# R111X.net
KiCad netlist of a schematic drawn in EAGLE
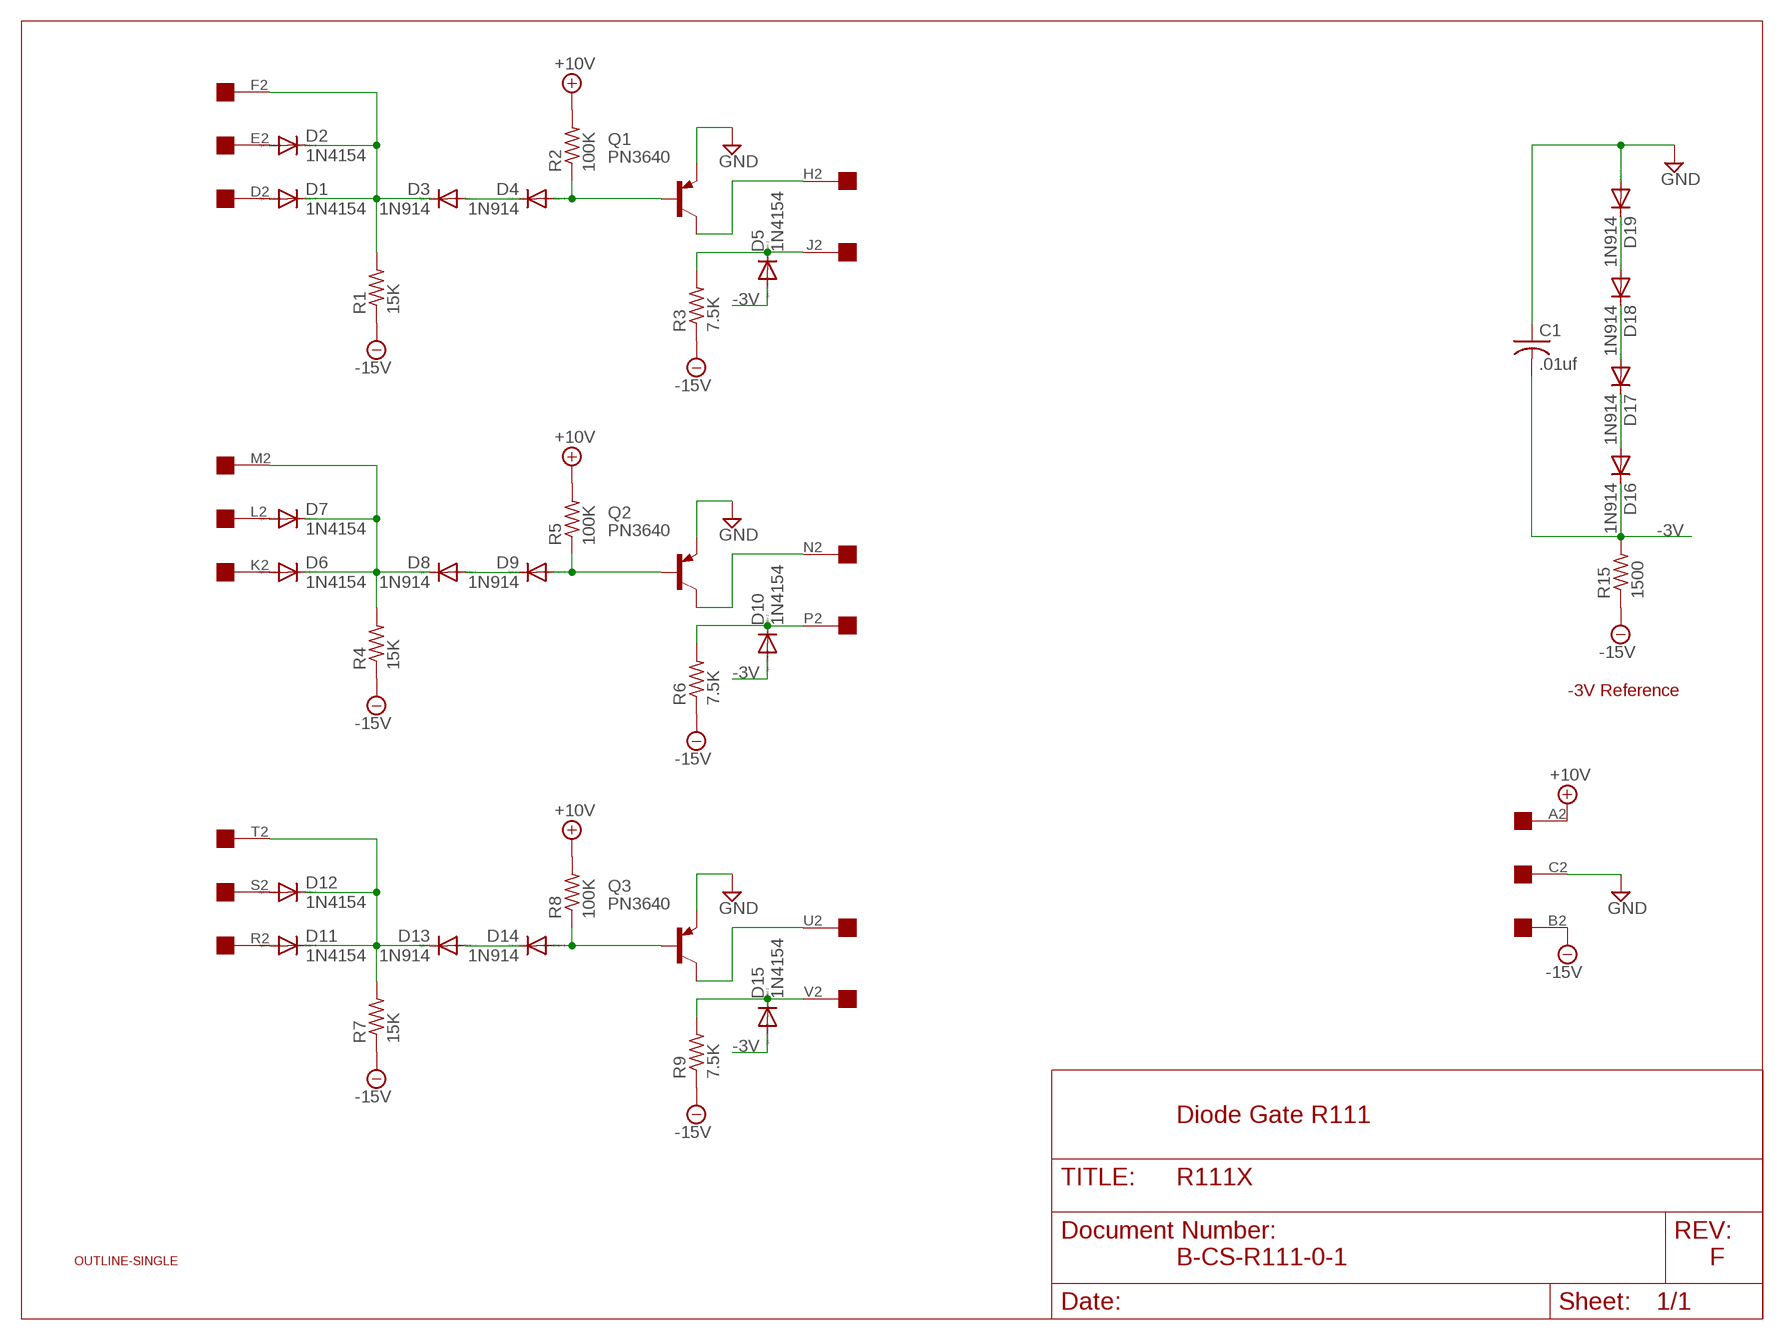
[diagram p0: schematic, sheet 1]

(export (version "E")
  (design (tool "Eeschema 10.0.6"))
  (components
    (comp (ref "C1")
      (value ".01uf")
      (footprint "eagle-import:C063-025X075")
      (libsource (lib "eagle-import") (part "C-US"))
    )
    (comp (ref "D1")
      (value "1N4154")
      (footprint "eagle-import:DO35-10")
      (libsource (lib "eagle-import") (part "1N4148DO35-10"))
    )
    (comp (ref "D2")
      (value "1N4154")
      (footprint "eagle-import:DO35-10")
      (libsource (lib "eagle-import") (part "1N4148DO35-10"))
    )
    (comp (ref "D3")
      (value "1N914")
      (footprint "eagle-import:DO35-10")
      (libsource (lib "eagle-import") (part "1N4148DO35-10"))
    )
    (comp (ref "D4")
      (value "1N914")
      (footprint "eagle-import:DO35-10")
      (libsource (lib "eagle-import") (part "1N4148DO35-10"))
    )
    (comp (ref "D5")
      (value "1N4154")
      (footprint "eagle-import:DO35-10")
      (libsource (lib "eagle-import") (part "1N4148DO35-10"))
    )
    (comp (ref "D6")
      (value "1N4154")
      (footprint "eagle-import:DO35-10")
      (libsource (lib "eagle-import") (part "1N4148DO35-10"))
    )
    (comp (ref "D7")
      (value "1N4154")
      (footprint "eagle-import:DO35-10")
      (libsource (lib "eagle-import") (part "1N4148DO35-10"))
    )
    (comp (ref "D8")
      (value "1N914")
      (footprint "eagle-import:DO35-10")
      (libsource (lib "eagle-import") (part "1N4148DO35-10"))
    )
    (comp (ref "D9")
      (value "1N914")
      (footprint "eagle-import:DO35-10")
      (libsource (lib "eagle-import") (part "1N4148DO35-10"))
    )
    (comp (ref "D10")
      (value "1N4154")
      (footprint "eagle-import:DO35-10")
      (libsource (lib "eagle-import") (part "1N4148DO35-10"))
    )
    (comp (ref "D11")
      (value "1N4154")
      (footprint "eagle-import:DO35-10")
      (libsource (lib "eagle-import") (part "1N4148DO35-10"))
    )
    (comp (ref "D12")
      (value "1N4154")
      (footprint "eagle-import:DO35-10")
      (libsource (lib "eagle-import") (part "1N4148DO35-10"))
    )
    (comp (ref "D13")
      (value "1N914")
      (footprint "eagle-import:DO35-10")
      (libsource (lib "eagle-import") (part "1N4148DO35-10"))
    )
    (comp (ref "D14")
      (value "1N914")
      (footprint "eagle-import:DO35-10")
      (libsource (lib "eagle-import") (part "1N4148DO35-10"))
    )
    (comp (ref "D15")
      (value "1N4154")
      (footprint "eagle-import:DO35-10")
      (libsource (lib "eagle-import") (part "1N4148DO35-10"))
    )
    (comp (ref "D16")
      (value "1N914")
      (footprint "eagle-import:DO35-10")
      (libsource (lib "eagle-import") (part "1N4148DO35-10"))
    )
    (comp (ref "D17")
      (value "1N914")
      (footprint "eagle-import:DO35-10")
      (libsource (lib "eagle-import") (part "1N4148DO35-10"))
    )
    (comp (ref "D18")
      (value "1N914")
      (footprint "eagle-import:DO35-10")
      (libsource (lib "eagle-import") (part "1N4148DO35-10"))
    )
    (comp (ref "D19")
      (value "1N914")
      (footprint "eagle-import:DO35-10")
      (libsource (lib "eagle-import") (part "1N4148DO35-10"))
    )
    (comp (ref "Q1")
      (value "PN3640")
      (footprint "eagle-import:TO39")
      (libsource (lib "eagle-import") (part "2N3637"))
    )
    (comp (ref "Q2")
      (value "PN3640")
      (footprint "eagle-import:TO39")
      (libsource (lib "eagle-import") (part "2N3637"))
    )
    (comp (ref "Q3")
      (value "PN3640")
      (footprint "eagle-import:TO39")
      (libsource (lib "eagle-import") (part "2N3637"))
    )
    (comp (ref "R1")
      (value "15K")
      (footprint "eagle-import:0207_10")
      (libsource (lib "eagle-import") (part "R-US_0207/10"))
    )
    (comp (ref "R2")
      (value "100K")
      (footprint "eagle-import:0207_10")
      (libsource (lib "eagle-import") (part "R-US_0207/10"))
    )
    (comp (ref "R3")
      (value "7.5K")
      (footprint "eagle-import:0207_10")
      (libsource (lib "eagle-import") (part "R-US_0207/10"))
    )
    (comp (ref "R4")
      (value "15K")
      (footprint "eagle-import:0207_10")
      (libsource (lib "eagle-import") (part "R-US_0207/10"))
    )
    (comp (ref "R5")
      (value "100K")
      (footprint "eagle-import:0207_10")
      (libsource (lib "eagle-import") (part "R-US_0207/10"))
    )
    (comp (ref "R6")
      (value "7.5K")
      (footprint "eagle-import:0207_10")
      (libsource (lib "eagle-import") (part "R-US_0207/10"))
    )
    (comp (ref "R7")
      (value "15K")
      (footprint "eagle-import:0207_10")
      (libsource (lib "eagle-import") (part "R-US_0207/10"))
    )
    (comp (ref "R8")
      (value "100K")
      (footprint "eagle-import:0207_10")
      (libsource (lib "eagle-import") (part "R-US_0207/10"))
    )
    (comp (ref "R9")
      (value "7.5K")
      (footprint "eagle-import:0207_10")
      (libsource (lib "eagle-import") (part "R-US_0207/10"))
    )
    (comp (ref "R15")
      (value "1500")
      (footprint "eagle-import:0207_10")
      (libsource (lib "eagle-import") (part "R-US_0207/10"))
    )
    (comp (ref "U$1")
      (value "OUTLINE-SINGLE")
      (footprint "eagle-import:SINGLE")
      (libsource (lib "eagle-import") (part "OUTLINE-SINGLE"))
    )
    (comp (ref "U$2")
      (value "EDGE-1")
      (footprint "eagle-import:EDGE-CON1")
      (libsource (lib "eagle-import") (part "EDGE-1"))
    )
  )
  (nets
    (net (code "1") (name "+10V") (class "Default")
      (node (ref "R2") (pin "2") (pinfunction "2_2") (pintype "passive"))
      (node (ref "R5") (pin "2") (pinfunction "2_2") (pintype "passive"))
      (node (ref "R8") (pin "2") (pinfunction "2_2") (pintype "passive"))
      (node (ref "U$2") (pin "A2") (pinfunction "1_A2") (pintype "bidirectional"))
    )
    (net (code "2") (name "-15V") (class "Default")
      (node (ref "R1") (pin "1") (pinfunction "1_1") (pintype "passive"))
      (node (ref "R15") (pin "1") (pinfunction "1_1") (pintype "passive"))
      (node (ref "R3") (pin "1") (pinfunction "1_1") (pintype "passive"))
      (node (ref "R4") (pin "1") (pinfunction "1_1") (pintype "passive"))
      (node (ref "R6") (pin "1") (pinfunction "1_1") (pintype "passive"))
      (node (ref "R7") (pin "1") (pinfunction "1_1") (pintype "passive"))
      (node (ref "R9") (pin "1") (pinfunction "1_1") (pintype "passive"))
      (node (ref "U$2") (pin "B2") (pinfunction "1_B2") (pintype "bidirectional"))
    )
    (net (code "3") (name "/-3V") (class "Default")
      (node (ref "C1") (pin "2") (pinfunction "2_2") (pintype "passive"))
      (node (ref "D10") (pin "A") (pinfunction "A_A") (pintype "passive"))
      (node (ref "D15") (pin "A") (pinfunction "A_A") (pintype "passive"))
      (node (ref "D16") (pin "C") (pinfunction "C_C") (pintype "passive"))
      (node (ref "D5") (pin "A") (pinfunction "A_A") (pintype "passive"))
      (node (ref "R15") (pin "2") (pinfunction "2_2") (pintype "passive"))
    )
    (net (code "4") (name "GND") (class "Default")
      (node (ref "C1") (pin "1") (pinfunction "1_1") (pintype "passive"))
      (node (ref "D19") (pin "A") (pinfunction "A_A") (pintype "passive"))
      (node (ref "Q1") (pin "1") (pinfunction "E_1") (pintype "passive"))
      (node (ref "Q2") (pin "1") (pinfunction "E_1") (pintype "passive"))
      (node (ref "Q3") (pin "1") (pinfunction "E_1") (pintype "passive"))
      (node (ref "U$2") (pin "C2") (pinfunction "1_C2") (pintype "bidirectional"))
    )
    (net (code "5") (name "Net-(D3-PadA)") (class "Default")
      (node (ref "D3") (pin "A") (pinfunction "A_A") (pintype "passive"))
      (node (ref "D4") (pin "C") (pinfunction "C_C") (pintype "passive"))
    )
    (net (code "6") (name "Net-(D8-PadA)") (class "Default")
      (node (ref "D8") (pin "A") (pinfunction "A_A") (pintype "passive"))
      (node (ref "D9") (pin "C") (pinfunction "C_C") (pintype "passive"))
    )
    (net (code "7") (name "Net-(D13-PadA)") (class "Default")
      (node (ref "D13") (pin "A") (pinfunction "A_A") (pintype "passive"))
      (node (ref "D14") (pin "C") (pinfunction "C_C") (pintype "passive"))
    )
    (net (code "8") (name "Net-(D16-PadA)") (class "Default")
      (node (ref "D16") (pin "A") (pinfunction "A_A") (pintype "passive"))
      (node (ref "D17") (pin "C") (pinfunction "C_C") (pintype "passive"))
    )
    (net (code "9") (name "Net-(D17-PadA)") (class "Default")
      (node (ref "D17") (pin "A") (pinfunction "A_A") (pintype "passive"))
      (node (ref "D18") (pin "C") (pinfunction "C_C") (pintype "passive"))
    )
    (net (code "10") (name "Net-(D18-PadA)") (class "Default")
      (node (ref "D18") (pin "A") (pinfunction "A_A") (pintype "passive"))
      (node (ref "D19") (pin "C") (pinfunction "C_C") (pintype "passive"))
    )
    (net (code "11") (name "Net-(Q1-B)") (class "Default")
      (node (ref "D4") (pin "A") (pinfunction "A_A") (pintype "passive"))
      (node (ref "Q1") (pin "2") (pinfunction "B_2") (pintype "passive"))
      (node (ref "R2") (pin "1") (pinfunction "1_1") (pintype "passive"))
    )
    (net (code "12") (name "Net-(Q1-C)") (class "Default")
      (node (ref "Q1") (pin "3") (pinfunction "C_3") (pintype "passive"))
      (node (ref "U$2") (pin "H2") (pinfunction "1_H2") (pintype "bidirectional"))
    )
    (net (code "13") (name "Net-(Q2-B)") (class "Default")
      (node (ref "D9") (pin "A") (pinfunction "A_A") (pintype "passive"))
      (node (ref "Q2") (pin "2") (pinfunction "B_2") (pintype "passive"))
      (node (ref "R5") (pin "1") (pinfunction "1_1") (pintype "passive"))
    )
    (net (code "14") (name "Net-(Q2-C)") (class "Default")
      (node (ref "Q2") (pin "3") (pinfunction "C_3") (pintype "passive"))
      (node (ref "U$2") (pin "N2") (pinfunction "1_N2") (pintype "bidirectional"))
    )
    (net (code "15") (name "Net-(Q3-B)") (class "Default")
      (node (ref "D14") (pin "A") (pinfunction "A_A") (pintype "passive"))
      (node (ref "Q3") (pin "2") (pinfunction "B_2") (pintype "passive"))
      (node (ref "R8") (pin "1") (pinfunction "1_1") (pintype "passive"))
    )
    (net (code "16") (name "Net-(Q3-C)") (class "Default")
      (node (ref "Q3") (pin "3") (pinfunction "C_3") (pintype "passive"))
      (node (ref "U$2") (pin "U2") (pinfunction "1_U2") (pintype "bidirectional"))
    )
    (net (code "17") (name "Net-(U$2D-1)") (class "Default")
      (node (ref "D1") (pin "A") (pinfunction "A_A") (pintype "passive"))
      (node (ref "U$2") (pin "D2") (pinfunction "1_D2") (pintype "bidirectional"))
    )
    (net (code "18") (name "Net-(U$2E-1)") (class "Default")
      (node (ref "D2") (pin "A") (pinfunction "A_A") (pintype "passive"))
      (node (ref "U$2") (pin "E2") (pinfunction "1_E2") (pintype "bidirectional"))
    )
    (net (code "19") (name "Net-(U$2F-1)") (class "Default")
      (node (ref "D1") (pin "C") (pinfunction "C_C") (pintype "passive"))
      (node (ref "D2") (pin "C") (pinfunction "C_C") (pintype "passive"))
      (node (ref "D3") (pin "C") (pinfunction "C_C") (pintype "passive"))
      (node (ref "R1") (pin "2") (pinfunction "2_2") (pintype "passive"))
      (node (ref "U$2") (pin "F2") (pinfunction "1_F2") (pintype "bidirectional"))
    )
    (net (code "20") (name "Net-(U$2H-1)") (class "Default")
      (node (ref "D5") (pin "C") (pinfunction "C_C") (pintype "passive"))
      (node (ref "R3") (pin "2") (pinfunction "2_2") (pintype "passive"))
      (node (ref "U$2") (pin "J2") (pinfunction "1_J2") (pintype "bidirectional"))
    )
    (net (code "21") (name "Net-(U$2I-1)") (class "Default")
      (node (ref "D6") (pin "A") (pinfunction "A_A") (pintype "passive"))
      (node (ref "U$2") (pin "K2") (pinfunction "1_K2") (pintype "bidirectional"))
    )
    (net (code "22") (name "Net-(U$2J-1)") (class "Default")
      (node (ref "D7") (pin "A") (pinfunction "A_A") (pintype "passive"))
      (node (ref "U$2") (pin "L2") (pinfunction "1_L2") (pintype "bidirectional"))
    )
    (net (code "23") (name "Net-(U$2K-1)") (class "Default")
      (node (ref "D6") (pin "C") (pinfunction "C_C") (pintype "passive"))
      (node (ref "D7") (pin "C") (pinfunction "C_C") (pintype "passive"))
      (node (ref "D8") (pin "C") (pinfunction "C_C") (pintype "passive"))
      (node (ref "R4") (pin "2") (pinfunction "2_2") (pintype "passive"))
      (node (ref "U$2") (pin "M2") (pinfunction "1_M2") (pintype "bidirectional"))
    )
    (net (code "24") (name "Net-(U$2M-1)") (class "Default")
      (node (ref "D10") (pin "C") (pinfunction "C_C") (pintype "passive"))
      (node (ref "R6") (pin "2") (pinfunction "2_2") (pintype "passive"))
      (node (ref "U$2") (pin "P2") (pinfunction "1_P2") (pintype "bidirectional"))
    )
    (net (code "25") (name "Net-(U$2N-1)") (class "Default")
      (node (ref "D11") (pin "A") (pinfunction "A_A") (pintype "passive"))
      (node (ref "U$2") (pin "R2") (pinfunction "1_R2") (pintype "bidirectional"))
    )
    (net (code "26") (name "Net-(U$2O-1)") (class "Default")
      (node (ref "D12") (pin "A") (pinfunction "A_A") (pintype "passive"))
      (node (ref "U$2") (pin "S2") (pinfunction "1_S2") (pintype "bidirectional"))
    )
    (net (code "27") (name "Net-(U$2P-1)") (class "Default")
      (node (ref "D11") (pin "C") (pinfunction "C_C") (pintype "passive"))
      (node (ref "D12") (pin "C") (pinfunction "C_C") (pintype "passive"))
      (node (ref "D13") (pin "C") (pinfunction "C_C") (pintype "passive"))
      (node (ref "R7") (pin "2") (pinfunction "2_2") (pintype "passive"))
      (node (ref "U$2") (pin "T2") (pinfunction "1_T2") (pintype "bidirectional"))
    )
    (net (code "28") (name "Net-(U$2R-1)") (class "Default")
      (node (ref "D15") (pin "C") (pinfunction "C_C") (pintype "passive"))
      (node (ref "R9") (pin "2") (pinfunction "2_2") (pintype "passive"))
      (node (ref "U$2") (pin "V2") (pinfunction "1_V2") (pintype "bidirectional"))
    )
  )
)
